# HeartSchem.net
KiCad netlist of a schematic drawn in Altium Designer
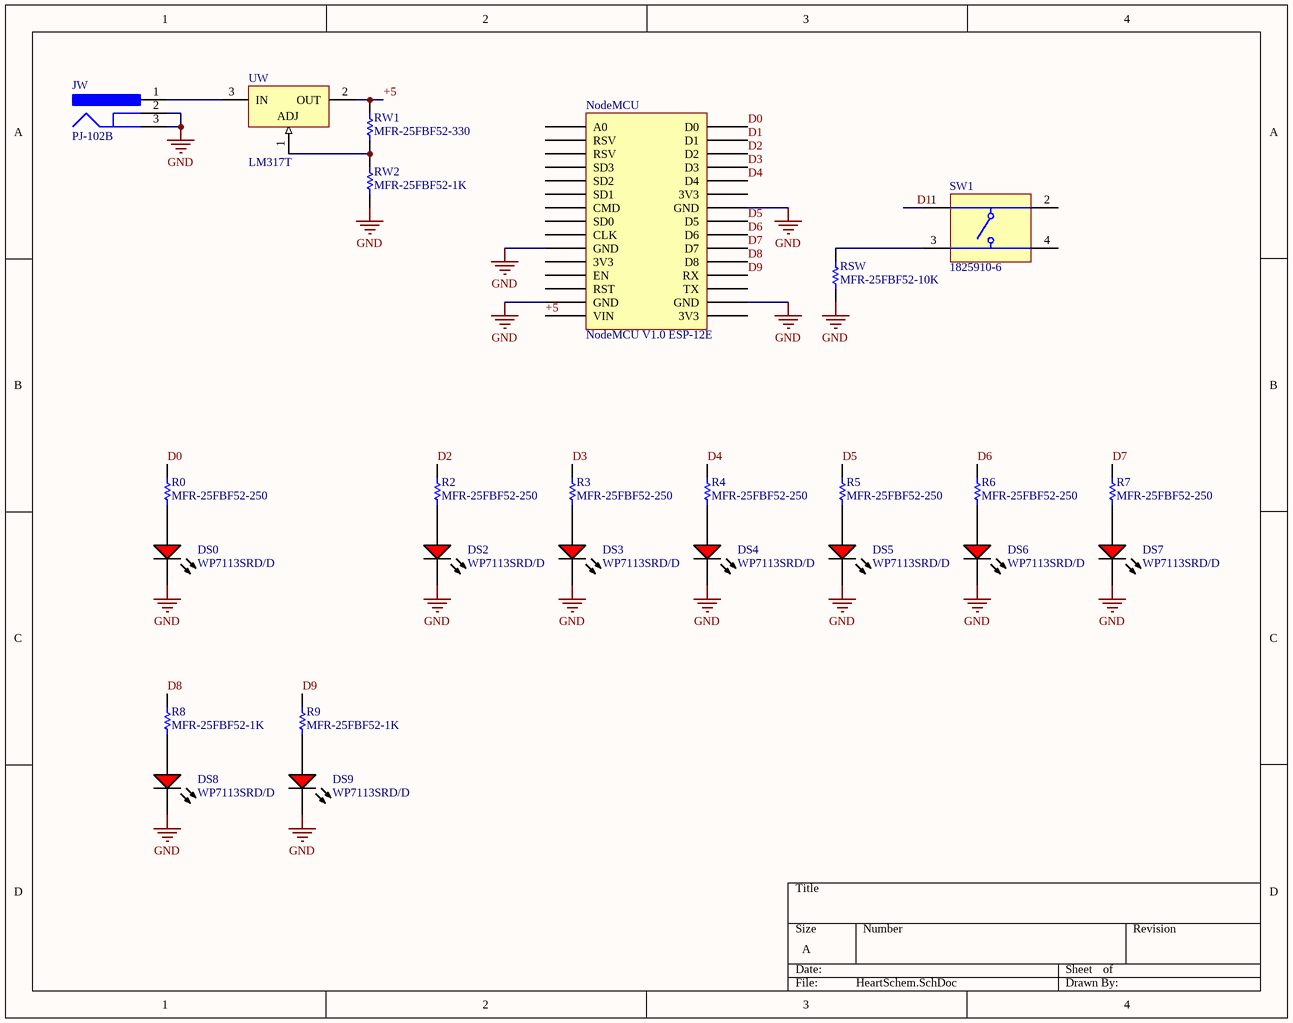
[diagram p0: HeartSchem.SchDoc]

(export (version "E")
  (design (tool "Eeschema 10.0.6"))
  (components
    (comp (ref "DS0")
      (value "WP7113SRD/D")
      (footprint "KING-WP7113SRDD_V")
      (description "The Super Bright Red Source Color Device, 1.85 V, -40 to 85 degC, 2-Pin THD, RoHS, Tape and Reel")
      (fields (field (name "MANUFACTURER") "Kingbright"))
      (libsource (lib "Christian Cipolletta's Workspace") (part "LED-RED-AK-2"))
    )
    (comp (ref "DS2")
      (value "WP7113SRD/D")
      (footprint "KING-WP7113SRDD_V")
      (description "The Super Bright Red Source Color Device, 1.85 V, -40 to 85 degC, 2-Pin THD, RoHS, Tape and Reel")
      (fields (field (name "MANUFACTURER") "Kingbright"))
      (libsource (lib "Christian Cipolletta's Workspace") (part "LED-RED-AK-2"))
    )
    (comp (ref "DS3")
      (value "WP7113SRD/D")
      (footprint "KING-WP7113SRDD_V")
      (description "The Super Bright Red Source Color Device, 1.85 V, -40 to 85 degC, 2-Pin THD, RoHS, Tape and Reel")
      (fields (field (name "MANUFACTURER") "Kingbright"))
      (libsource (lib "Christian Cipolletta's Workspace") (part "LED-RED-AK-2"))
    )
    (comp (ref "DS4")
      (value "WP7113SRD/D")
      (footprint "KING-WP7113SRDD_V")
      (description "The Super Bright Red Source Color Device, 1.85 V, -40 to 85 degC, 2-Pin THD, RoHS, Tape and Reel")
      (fields (field (name "MANUFACTURER") "Kingbright"))
      (libsource (lib "Christian Cipolletta's Workspace") (part "LED-RED-AK-2"))
    )
    (comp (ref "DS5")
      (value "WP7113SRD/D")
      (footprint "KING-WP7113SRDD_V")
      (description "The Super Bright Red Source Color Device, 1.85 V, -40 to 85 degC, 2-Pin THD, RoHS, Tape and Reel")
      (fields (field (name "MANUFACTURER") "Kingbright"))
      (libsource (lib "Christian Cipolletta's Workspace") (part "LED-RED-AK-2"))
    )
    (comp (ref "DS6")
      (value "WP7113SRD/D")
      (footprint "KING-WP7113SRDD_V")
      (description "The Super Bright Red Source Color Device, 1.85 V, -40 to 85 degC, 2-Pin THD, RoHS, Tape and Reel")
      (fields (field (name "MANUFACTURER") "Kingbright"))
      (libsource (lib "Christian Cipolletta's Workspace") (part "LED-RED-AK-2"))
    )
    (comp (ref "DS7")
      (value "WP7113SRD/D")
      (footprint "KING-WP7113SRDD_V")
      (description "The Super Bright Red Source Color Device, 1.85 V, -40 to 85 degC, 2-Pin THD, RoHS, Tape and Reel")
      (fields (field (name "MANUFACTURER") "Kingbright"))
      (libsource (lib "Christian Cipolletta's Workspace") (part "LED-RED-AK-2"))
    )
    (comp (ref "DS8")
      (value "WP7113SRD/D")
      (footprint "KING-WP7113SRDD_V")
      (description "The Super Bright Red Source Color Device, 1.85 V, -40 to 85 degC, 2-Pin THD, RoHS, Tape and Reel")
      (fields (field (name "MANUFACTURER") "Kingbright"))
      (libsource (lib "Christian Cipolletta's Workspace") (part "LED-RED-AK-2"))
    )
    (comp (ref "DS9")
      (value "WP7113SRD/D")
      (footprint "KING-WP7113SRDD_V")
      (description "The Super Bright Red Source Color Device, 1.85 V, -40 to 85 degC, 2-Pin THD, RoHS, Tape and Reel")
      (fields (field (name "MANUFACTURER") "Kingbright"))
      (libsource (lib "Christian Cipolletta's Workspace") (part "LED-RED-AK-2"))
    )
    (comp (ref "JW")
      (value "PJ-102B")
      (footprint "CUI-PJ-102B_V")
      (fields (field (name "MANUFACTURER") "CUIInc."))
      (libsource (lib "Altium Content Vault") (part "JACK-2CD3-RN"))
    )
    (comp (ref "NodeMCU")
      (value "NodeMCU V1.0 ESP-12E")
      (footprint "NodeMCU V1.0 ESP-12E")
      (description "NodeMCU V1.0 ESP8266 (ESP-12E)")
      (libsource (lib "nodemcu") (part "NodeMCU V1.0 ESP-12E"))
    )
    (comp (ref "R0")
      (value "MFR-25FBF52-250")
      (footprint "RESA60-630X240")
      (description "Axial Resistor, 1 KOhm, +/- 1%, 250 mW, -55 to 155 degC, 2-Pin THD, RoHS, Bulk")
      (fields (field (name "TOLERANCE") "1%"))
      (libsource (lib "Altium Content Vault") (part "RES-2"))
    )
    (comp (ref "R2")
      (value "MFR-25FBF52-250")
      (footprint "RESA60-630X240")
      (description "Axial Resistor, 1 KOhm, +/- 1%, 250 mW, -55 to 155 degC, 2-Pin THD, RoHS, Bulk")
      (fields (field (name "TOLERANCE") "1%"))
      (libsource (lib "Altium Content Vault") (part "RES-2"))
    )
    (comp (ref "R3")
      (value "MFR-25FBF52-250")
      (footprint "RESA60-630X240")
      (description "Axial Resistor, 1 KOhm, +/- 1%, 250 mW, -55 to 155 degC, 2-Pin THD, RoHS, Bulk")
      (fields (field (name "TOLERANCE") "1%"))
      (libsource (lib "Altium Content Vault") (part "RES-2"))
    )
    (comp (ref "R4")
      (value "MFR-25FBF52-250")
      (footprint "RESA60-630X240")
      (description "Axial Resistor, 1 KOhm, +/- 1%, 250 mW, -55 to 155 degC, 2-Pin THD, RoHS, Bulk")
      (fields (field (name "TOLERANCE") "1%"))
      (libsource (lib "Altium Content Vault") (part "RES-2"))
    )
    (comp (ref "R5")
      (value "MFR-25FBF52-250")
      (footprint "RESA60-630X240")
      (description "Axial Resistor, 1 KOhm, +/- 1%, 250 mW, -55 to 155 degC, 2-Pin THD, RoHS, Bulk")
      (fields (field (name "TOLERANCE") "1%"))
      (libsource (lib "Altium Content Vault") (part "RES-2"))
    )
    (comp (ref "R6")
      (value "MFR-25FBF52-250")
      (footprint "RESA60-630X240")
      (description "Axial Resistor, 1 KOhm, +/- 1%, 250 mW, -55 to 155 degC, 2-Pin THD, RoHS, Bulk")
      (fields (field (name "TOLERANCE") "1%"))
      (libsource (lib "Altium Content Vault") (part "RES-2"))
    )
    (comp (ref "R7")
      (value "MFR-25FBF52-250")
      (footprint "RESA60-630X240")
      (description "Axial Resistor, 1 KOhm, +/- 1%, 250 mW, -55 to 155 degC, 2-Pin THD, RoHS, Bulk")
      (fields (field (name "TOLERANCE") "1%"))
      (libsource (lib "Altium Content Vault") (part "RES-2"))
    )
    (comp (ref "R8")
      (value "MFR-25FBF52-1K")
      (footprint "RESA60-630X240")
      (description "Axial Resistor, 1 KOhm, +/- 1%, 250 mW, -55 to 155 degC, 2-Pin THD, RoHS, Bulk")
      (fields (field (name "TOLERANCE") "1%"))
      (libsource (lib "Altium Content Vault") (part "RES-2"))
    )
    (comp (ref "R9")
      (value "MFR-25FBF52-1K")
      (footprint "RESA60-630X240")
      (description "Axial Resistor, 1 KOhm, +/- 1%, 250 mW, -55 to 155 degC, 2-Pin THD, RoHS, Bulk")
      (fields (field (name "TOLERANCE") "1%"))
      (libsource (lib "Altium Content Vault") (part "RES-2"))
    )
    (comp (ref "RSW")
      (value "MFR-25FBF52-10K")
      (footprint "RESA60-630X240")
      (description "Axial Resistor, 1 KOhm, +/- 1%, 250 mW, -55 to 155 degC, 2-Pin THD, RoHS, Bulk")
      (fields (field (name "TOLERANCE") "1%"))
      (libsource (lib "Altium Content Vault") (part "RES-2"))
    )
    (comp (ref "RW1")
      (value "MFR-25FBF52-330")
      (footprint "RESA60-630X240")
      (description "Axial Resistor, 1 KOhm, +/- 1%, 250 mW, -55 to 155 degC, 2-Pin THD, RoHS, Bulk")
      (fields (field (name "TOLERANCE") "1%"))
      (libsource (lib "Altium Content Vault") (part "RES-2"))
    )
    (comp (ref "RW2")
      (value "MFR-25FBF52-1K")
      (footprint "RESA60-630X240")
      (description "Axial Resistor, 1 KOhm, +/- 1%, 250 mW, -55 to 155 degC, 2-Pin THD, RoHS, Bulk")
      (fields (field (name "TOLERANCE") "1%"))
      (libsource (lib "Altium Content Vault") (part "RES-2"))
    )
    (comp (ref "SW1")
      (value "1825910-6")
      (footprint "TECO-1825910-6_V")
      (description "Tact Switch, SPST-NO, 0.05 A, -35 to 85 degC, 4-Pin THD, RoHS, Bulk")
      (fields (field (name "MANUFACTURER") "TE Connectivity"))
      (libsource (lib "Altium Content Vault") (part "SW-SPST-4_A"))
    )
    (comp (ref "UW")
      (value "LM317T")
      (footprint "TO-220")
      (description "1.5A, 1.2V to 37V Adjustable Voltage Regulator, 3-Pin TO-220")
      (libsource (lib "Altium Content Vault") (part "PM-REG-117-SIL3"))
    )
  )
  (nets
    (net (code "1") (name "/+5") (class "Default")
      (node (ref "NodeMCU") (pin "VIN") (pinfunction "VIN_VIN") (pintype "passive"))
      (node (ref "RW1") (pin "1") (pinfunction "1_1") (pintype "passive"))
      (node (ref "UW") (pin "2") (pinfunction "OUT_2") (pintype "power_in"))
    )
    (net (code "2") (name "/D0") (class "Default")
      (node (ref "NodeMCU") (pin "D0") (pinfunction "D0_D0") (pintype "passive"))
      (node (ref "R0") (pin "1") (pinfunction "1_1") (pintype "passive"))
    )
    (net (code "3") (name "/D1") (class "Default")
      (node (ref "NodeMCU") (pin "D1") (pinfunction "D1_D1") (pintype "passive"))
      (node (ref "SW1") (pin "1") (pinfunction "1_1") (pintype "passive"))
    )
    (net (code "4") (name "/D2") (class "Default")
      (node (ref "NodeMCU") (pin "D2") (pinfunction "D2_D2") (pintype "passive"))
      (node (ref "R2") (pin "1") (pinfunction "1_1") (pintype "passive"))
    )
    (net (code "5") (name "/D3") (class "Default")
      (node (ref "NodeMCU") (pin "D3") (pinfunction "D3_D3") (pintype "passive"))
      (node (ref "R3") (pin "1") (pinfunction "1_1") (pintype "passive"))
    )
    (net (code "6") (name "/D4") (class "Default")
      (node (ref "NodeMCU") (pin "D4") (pinfunction "D4_D4") (pintype "passive"))
      (node (ref "R4") (pin "1") (pinfunction "1_1") (pintype "passive"))
    )
    (net (code "7") (name "/D5") (class "Default")
      (node (ref "NodeMCU") (pin "D5") (pinfunction "D5_D5") (pintype "passive"))
      (node (ref "R5") (pin "1") (pinfunction "1_1") (pintype "passive"))
    )
    (net (code "8") (name "/D6") (class "Default")
      (node (ref "NodeMCU") (pin "D6") (pinfunction "D6_D6") (pintype "passive"))
      (node (ref "R6") (pin "1") (pinfunction "1_1") (pintype "passive"))
    )
    (net (code "9") (name "/D7") (class "Default")
      (node (ref "NodeMCU") (pin "D7") (pinfunction "D7_D7") (pintype "passive"))
      (node (ref "R7") (pin "1") (pinfunction "1_1") (pintype "passive"))
    )
    (net (code "10") (name "/D8") (class "Default")
      (node (ref "NodeMCU") (pin "D8") (pinfunction "D8_D8") (pintype "passive"))
      (node (ref "R8") (pin "1") (pinfunction "1_1") (pintype "passive"))
    )
    (net (code "11") (name "/D9") (class "Default")
      (node (ref "NodeMCU") (pin "RX") (pinfunction "RX_RX") (pintype "passive"))
      (node (ref "R9") (pin "1") (pinfunction "1_1") (pintype "passive"))
    )
    (net (code "12") (name "GND") (class "Default")
      (node (ref "DS0") (pin "2") (pinfunction "K_2") (pintype "passive"))
      (node (ref "DS2") (pin "2") (pinfunction "K_2") (pintype "passive"))
      (node (ref "DS3") (pin "2") (pinfunction "K_2") (pintype "passive"))
      (node (ref "DS4") (pin "2") (pinfunction "K_2") (pintype "passive"))
      (node (ref "DS5") (pin "2") (pinfunction "K_2") (pintype "passive"))
      (node (ref "DS6") (pin "2") (pinfunction "K_2") (pintype "passive"))
      (node (ref "DS7") (pin "2") (pinfunction "K_2") (pintype "passive"))
      (node (ref "DS8") (pin "2") (pinfunction "K_2") (pintype "passive"))
      (node (ref "DS9") (pin "2") (pinfunction "K_2") (pintype "passive"))
      (node (ref "JW") (pin "2") (pinfunction "2_2") (pintype "passive"))
      (node (ref "JW") (pin "3") (pinfunction "3_3") (pintype "passive"))
      (node (ref "NodeMCU") (pin "GND") (pinfunction "GND_GND") (pintype "passive"))
      (node (ref "RSW") (pin "2") (pinfunction "2_2") (pintype "passive"))
      (node (ref "RW2") (pin "2") (pinfunction "2_2") (pintype "passive"))
    )
    (net (code "13") (name "Net-(DS0-A)") (class "Default")
      (node (ref "DS0") (pin "1") (pinfunction "A_1") (pintype "passive"))
      (node (ref "R0") (pin "2") (pinfunction "2_2") (pintype "passive"))
    )
    (net (code "14") (name "Net-(DS2-A)") (class "Default")
      (node (ref "DS2") (pin "1") (pinfunction "A_1") (pintype "passive"))
      (node (ref "R2") (pin "2") (pinfunction "2_2") (pintype "passive"))
    )
    (net (code "15") (name "Net-(DS3-A)") (class "Default")
      (node (ref "DS3") (pin "1") (pinfunction "A_1") (pintype "passive"))
      (node (ref "R3") (pin "2") (pinfunction "2_2") (pintype "passive"))
    )
    (net (code "16") (name "Net-(DS4-A)") (class "Default")
      (node (ref "DS4") (pin "1") (pinfunction "A_1") (pintype "passive"))
      (node (ref "R4") (pin "2") (pinfunction "2_2") (pintype "passive"))
    )
    (net (code "17") (name "Net-(DS5-A)") (class "Default")
      (node (ref "DS5") (pin "1") (pinfunction "A_1") (pintype "passive"))
      (node (ref "R5") (pin "2") (pinfunction "2_2") (pintype "passive"))
    )
    (net (code "18") (name "Net-(DS6-A)") (class "Default")
      (node (ref "DS6") (pin "1") (pinfunction "A_1") (pintype "passive"))
      (node (ref "R6") (pin "2") (pinfunction "2_2") (pintype "passive"))
    )
    (net (code "19") (name "Net-(DS7-A)") (class "Default")
      (node (ref "DS7") (pin "1") (pinfunction "A_1") (pintype "passive"))
      (node (ref "R7") (pin "2") (pinfunction "2_2") (pintype "passive"))
    )
    (net (code "20") (name "Net-(DS8-A)") (class "Default")
      (node (ref "DS8") (pin "1") (pinfunction "A_1") (pintype "passive"))
      (node (ref "R8") (pin "2") (pinfunction "2_2") (pintype "passive"))
    )
    (net (code "21") (name "Net-(DS9-A)") (class "Default")
      (node (ref "DS9") (pin "1") (pinfunction "A_1") (pintype "passive"))
      (node (ref "R9") (pin "2") (pinfunction "2_2") (pintype "passive"))
    )
    (net (code "22") (name "Net-(RSW-Pad1)") (class "Default")
      (node (ref "RSW") (pin "1") (pinfunction "1_1") (pintype "passive"))
      (node (ref "SW1") (pin "3") (pinfunction "3_3") (pintype "passive"))
    )
    (net (code "23") (name "Net-(UW-ADJ)") (class "Default")
      (node (ref "RW1") (pin "2") (pinfunction "2_2") (pintype "passive"))
      (node (ref "RW2") (pin "1") (pinfunction "1_1") (pintype "passive"))
      (node (ref "UW") (pin "1") (pinfunction "ADJ_1") (pintype "input"))
    )
    (net (code "24") (name "Net-(UW-IN)") (class "Default")
      (node (ref "JW") (pin "1") (pinfunction "1_1") (pintype "passive"))
      (node (ref "UW") (pin "3") (pinfunction "IN_3") (pintype "power_in"))
    )
    (net (code "25") (name "unconnected-(NodeMCU-Pad3V3)") (class "Default")
      (node (ref "NodeMCU") (pin "3V3") (pinfunction "3V3_3V3") (pintype "passive"))
    )
    (net (code "26") (name "unconnected-(NodeMCU-Pad3V3)_1") (class "Default")
      (node (ref "NodeMCU") (pin "3V3") (pinfunction "3V3_3V3") (pintype "passive"))
    )
    (net (code "27") (name "unconnected-(NodeMCU-Pad3V3)_2") (class "Default")
      (node (ref "NodeMCU") (pin "3V3") (pinfunction "3V3_3V3") (pintype "passive"))
    )
    (net (code "28") (name "unconnected-(NodeMCU-PadA0)") (class "Default")
      (node (ref "NodeMCU") (pin "A0") (pinfunction "A0_A0") (pintype "passive"))
    )
    (net (code "29") (name "unconnected-(NodeMCU-PadCLK)") (class "Default")
      (node (ref "NodeMCU") (pin "CLK") (pinfunction "CLK_CLK") (pintype "passive"))
    )
    (net (code "30") (name "unconnected-(NodeMCU-PadCMD)") (class "Default")
      (node (ref "NodeMCU") (pin "CMD") (pinfunction "CMD_CMD") (pintype "passive"))
    )
    (net (code "31") (name "unconnected-(NodeMCU-PadEN)") (class "Default")
      (node (ref "NodeMCU") (pin "EN") (pinfunction "EN_EN") (pintype "passive"))
    )
    (net (code "32") (name "unconnected-(NodeMCU-PadRST)") (class "Default")
      (node (ref "NodeMCU") (pin "RST") (pinfunction "RST_RST") (pintype "passive"))
    )
    (net (code "33") (name "unconnected-(NodeMCU-PadRSV)") (class "Default")
      (node (ref "NodeMCU") (pin "RSV") (pinfunction "RSV_RSV") (pintype "passive"))
    )
    (net (code "34") (name "unconnected-(NodeMCU-PadRSV)_1") (class "Default")
      (node (ref "NodeMCU") (pin "RSV") (pinfunction "RSV_RSV") (pintype "passive"))
    )
    (net (code "35") (name "unconnected-(NodeMCU-PadSD0)") (class "Default")
      (node (ref "NodeMCU") (pin "SD0") (pinfunction "SD0_SD0") (pintype "passive"))
    )
    (net (code "36") (name "unconnected-(NodeMCU-PadSD1)") (class "Default")
      (node (ref "NodeMCU") (pin "SD1") (pinfunction "SD1_SD1") (pintype "passive"))
    )
    (net (code "37") (name "unconnected-(NodeMCU-PadSD2)") (class "Default")
      (node (ref "NodeMCU") (pin "SD2") (pinfunction "SD2_SD2") (pintype "passive"))
    )
    (net (code "38") (name "unconnected-(NodeMCU-PadSD3)") (class "Default")
      (node (ref "NodeMCU") (pin "SD3") (pinfunction "SD3_SD3") (pintype "passive"))
    )
    (net (code "39") (name "unconnected-(NodeMCU-PadTX)") (class "Default")
      (node (ref "NodeMCU") (pin "TX") (pinfunction "TX_TX") (pintype "passive"))
    )
    (net (code "40") (name "unconnected-(SW1-Pad2)") (class "Default")
      (node (ref "SW1") (pin "2") (pinfunction "2_2") (pintype "passive"))
    )
    (net (code "41") (name "unconnected-(SW1-Pad4)") (class "Default")
      (node (ref "SW1") (pin "4") (pinfunction "4_4") (pintype "passive"))
    )
  )
)
